# RHD2164_USBC.net
KiCad netlist of a schematic drawn in Altium Designer
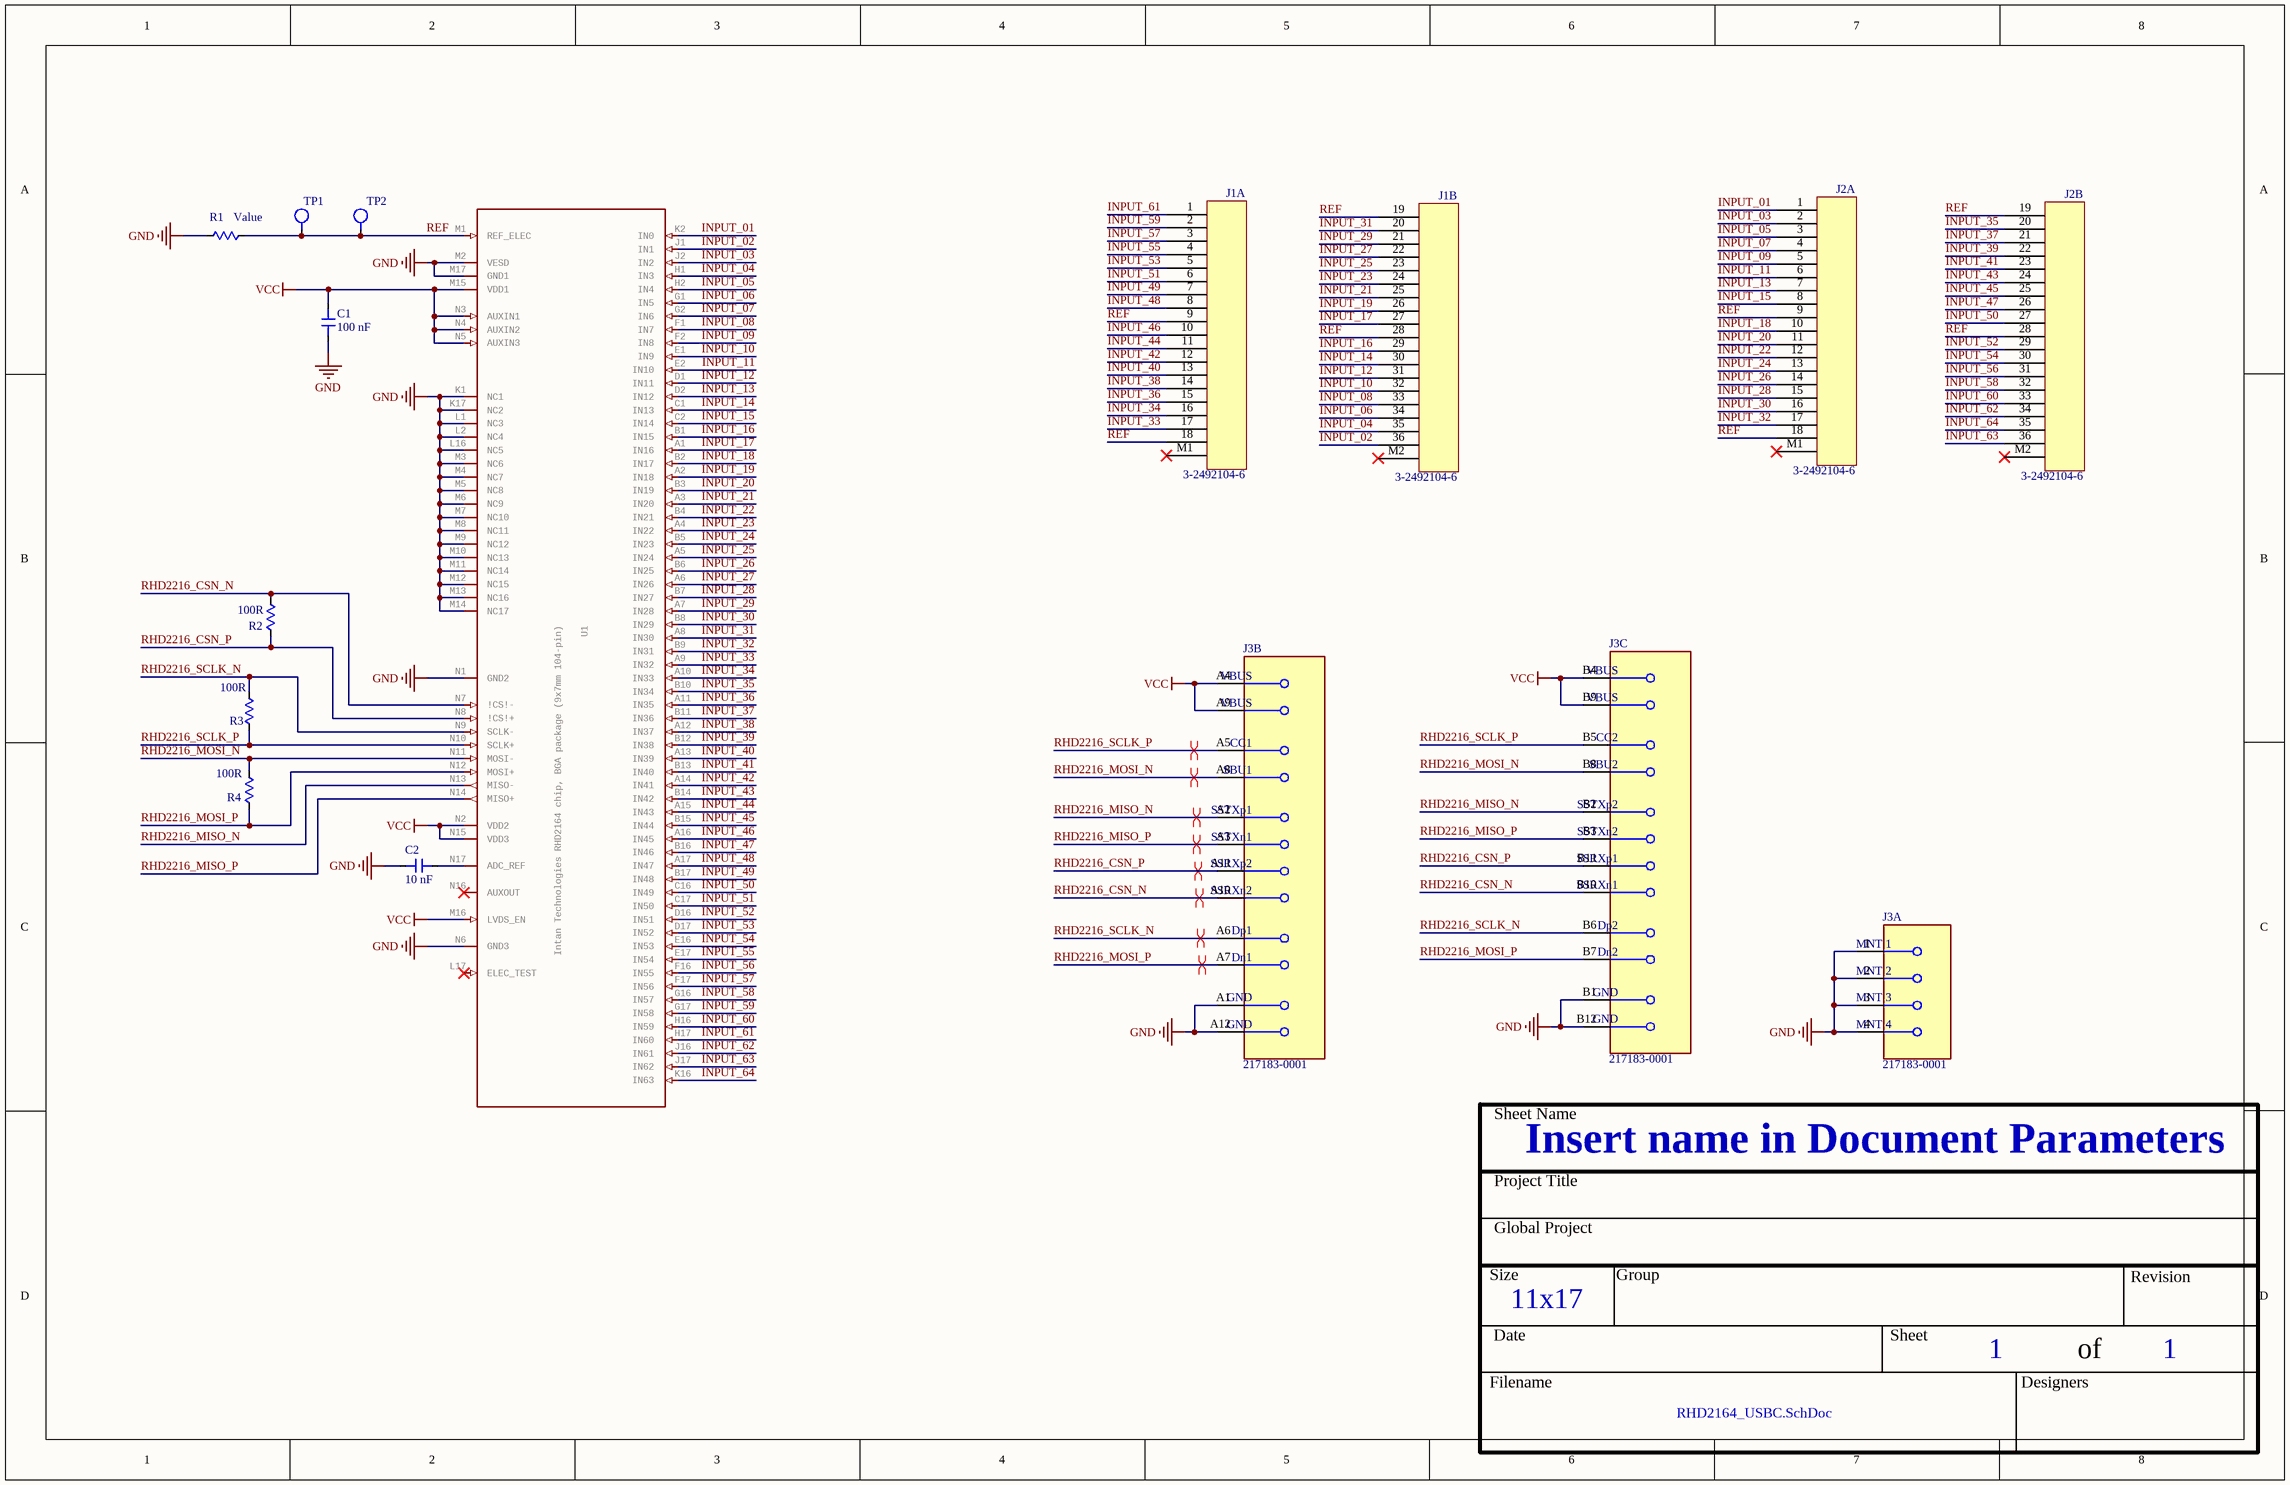
[diagram p0: RHD2164_USBC.SchDoc]

(export (version "E")
  (design (tool "Eeschema 10.0.6"))
  (components
    (comp (ref "C1")
      (value "100 nF")
      (footprint "0402_CAPACITOR")
      (description "Capacitor")
      (libsource (lib "RHD2164_USBC_V2") (part "Capacitor"))
    )
    (comp (ref "C2")
      (value "10 nF")
      (footprint "0402_CAPACITOR")
      (description "Capacitor")
      (libsource (lib "RHD2164_USBC_V2") (part "Capacitor"))
    )
    (comp (ref "J1")
      (value "3-2492104-6")
      (footprint "CON_ZIF_RA_36POS")
      (description "36 Position FPC Connector Contacts, Bottom 0.020\" (0.50mm) Surface Mount, Right Angle")
      (libsource (lib "RHD2164_USBC_V2") (part "CON_ZIF_RA_36POS"))
    )
    (comp (ref "J2")
      (value "3-2492104-6")
      (footprint "CON_ZIF_RA_36POS")
      (description "36 Position FPC Connector Contacts, Bottom 0.020\" (0.50mm) Surface Mount, Right Angle")
      (libsource (lib "RHD2164_USBC_V2") (part "CON_ZIF_RA_36POS"))
    )
    (comp (ref "J3")
      (value "217183-0001")
      (footprint "FP-217183-0001-MFG")
      (libsource (lib "Connectors") (part "CON_USBC_TH_SMT"))
    )
    (comp (ref "R1")
      (value "Value")
      (footprint "0402_Resistor")
      (description "Resistor")
      (libsource (lib "RHD2164_USBC_V2") (part "Resistor"))
    )
    (comp (ref "R2")
      (value "100R")
      (footprint "0402_Resistor")
      (description "Resistor")
      (libsource (lib "RHD2164_USBC_V2") (part "Resistor"))
    )
    (comp (ref "R3")
      (value "100R")
      (footprint "0402_Resistor")
      (description "Resistor")
      (libsource (lib "RHD2164_USBC_V2") (part "Resistor"))
    )
    (comp (ref "R4")
      (value "100R")
      (footprint "0402_Resistor")
      (description "Resistor")
      (libsource (lib "RHD2164_USBC_V2") (part "Resistor"))
    )
    (comp (ref "TP1")
      (value "TP_Small")
      (footprint "TP_Small_M2")
      (libsource (lib "RHD2164_USBC_V2") (part "TP_Small"))
    )
    (comp (ref "TP2")
      (value "TP_Small")
      (footprint "TP_Small_M2")
      (libsource (lib "RHD2164_USBC_V2") (part "TP_Small"))
    )
    (comp (ref "U1")
      (value "Intan Technologies RHD2164 chip, BGA package (9x7mm 104-pin)")
      (footprint "RHD2164_BGA")
      (libsource (lib "RHD2164_USBC_V2") (part "RHD2164_BGA_BGA"))
    )
  )
  (nets
    (net (code "1") (name "/INPUT_01") (class "Default")
      (node (ref "J2") (pin "1") (pinfunction "1_1") (pintype "passive"))
      (node (ref "U1") (pin "K2") (pinfunction "IN0_K2") (pintype "input"))
    )
    (net (code "2") (name "/INPUT_02") (class "Default")
      (node (ref "J1") (pin "36") (pinfunction "36_36") (pintype "passive"))
      (node (ref "U1") (pin "J1") (pinfunction "IN1_J1") (pintype "input"))
    )
    (net (code "3") (name "/INPUT_03") (class "Default")
      (node (ref "J2") (pin "2") (pinfunction "2_2") (pintype "passive"))
      (node (ref "U1") (pin "J2") (pinfunction "IN2_J2") (pintype "input"))
    )
    (net (code "4") (name "/INPUT_04") (class "Default")
      (node (ref "J1") (pin "35") (pinfunction "35_35") (pintype "passive"))
      (node (ref "U1") (pin "H1") (pinfunction "IN3_H1") (pintype "input"))
    )
    (net (code "5") (name "/INPUT_05") (class "Default")
      (node (ref "J2") (pin "3") (pinfunction "3_3") (pintype "passive"))
      (node (ref "U1") (pin "H2") (pinfunction "IN4_H2") (pintype "input"))
    )
    (net (code "6") (name "/INPUT_06") (class "Default")
      (node (ref "J1") (pin "34") (pinfunction "34_34") (pintype "passive"))
      (node (ref "U1") (pin "G1") (pinfunction "IN5_G1") (pintype "input"))
    )
    (net (code "7") (name "/INPUT_07") (class "Default")
      (node (ref "J2") (pin "4") (pinfunction "4_4") (pintype "passive"))
      (node (ref "U1") (pin "G2") (pinfunction "IN6_G2") (pintype "input"))
    )
    (net (code "8") (name "/INPUT_08") (class "Default")
      (node (ref "J1") (pin "33") (pinfunction "33_33") (pintype "passive"))
      (node (ref "U1") (pin "F1") (pinfunction "IN7_F1") (pintype "input"))
    )
    (net (code "9") (name "/INPUT_09") (class "Default")
      (node (ref "J2") (pin "5") (pinfunction "5_5") (pintype "passive"))
      (node (ref "U1") (pin "F2") (pinfunction "IN8_F2") (pintype "input"))
    )
    (net (code "10") (name "/INPUT_10") (class "Default")
      (node (ref "J1") (pin "32") (pinfunction "32_32") (pintype "passive"))
      (node (ref "U1") (pin "E1") (pinfunction "IN9_E1") (pintype "input"))
    )
    (net (code "11") (name "/INPUT_11") (class "Default")
      (node (ref "J2") (pin "6") (pinfunction "6_6") (pintype "passive"))
      (node (ref "U1") (pin "E2") (pinfunction "IN10_E2") (pintype "input"))
    )
    (net (code "12") (name "/INPUT_12") (class "Default")
      (node (ref "J1") (pin "31") (pinfunction "31_31") (pintype "passive"))
      (node (ref "U1") (pin "D1") (pinfunction "IN11_D1") (pintype "input"))
    )
    (net (code "13") (name "/INPUT_13") (class "Default")
      (node (ref "J2") (pin "7") (pinfunction "7_7") (pintype "passive"))
      (node (ref "U1") (pin "D2") (pinfunction "IN12_D2") (pintype "input"))
    )
    (net (code "14") (name "/INPUT_14") (class "Default")
      (node (ref "J1") (pin "30") (pinfunction "30_30") (pintype "passive"))
      (node (ref "U1") (pin "C1") (pinfunction "IN13_C1") (pintype "input"))
    )
    (net (code "15") (name "/INPUT_15") (class "Default")
      (node (ref "J2") (pin "8") (pinfunction "8_8") (pintype "passive"))
      (node (ref "U1") (pin "C2") (pinfunction "IN14_C2") (pintype "input"))
    )
    (net (code "16") (name "/INPUT_16") (class "Default")
      (node (ref "J1") (pin "29") (pinfunction "29_29") (pintype "passive"))
      (node (ref "U1") (pin "B1") (pinfunction "IN15_B1") (pintype "input"))
    )
    (net (code "17") (name "/INPUT_17") (class "Default")
      (node (ref "J1") (pin "27") (pinfunction "27_27") (pintype "passive"))
      (node (ref "U1") (pin "A1") (pinfunction "IN16_A1") (pintype "input"))
    )
    (net (code "18") (name "/INPUT_18") (class "Default")
      (node (ref "J2") (pin "10") (pinfunction "10_10") (pintype "passive"))
      (node (ref "U1") (pin "B2") (pinfunction "IN17_B2") (pintype "input"))
    )
    (net (code "19") (name "/INPUT_19") (class "Default")
      (node (ref "J1") (pin "26") (pinfunction "26_26") (pintype "passive"))
      (node (ref "U1") (pin "A2") (pinfunction "IN18_A2") (pintype "input"))
    )
    (net (code "20") (name "/INPUT_20") (class "Default")
      (node (ref "J2") (pin "11") (pinfunction "11_11") (pintype "passive"))
      (node (ref "U1") (pin "B3") (pinfunction "IN19_B3") (pintype "input"))
    )
    (net (code "21") (name "/INPUT_21") (class "Default")
      (node (ref "J1") (pin "25") (pinfunction "25_25") (pintype "passive"))
      (node (ref "U1") (pin "A3") (pinfunction "IN20_A3") (pintype "input"))
    )
    (net (code "22") (name "/INPUT_22") (class "Default")
      (node (ref "J2") (pin "12") (pinfunction "12_12") (pintype "passive"))
      (node (ref "U1") (pin "B4") (pinfunction "IN21_B4") (pintype "input"))
    )
    (net (code "23") (name "/INPUT_23") (class "Default")
      (node (ref "J1") (pin "24") (pinfunction "24_24") (pintype "passive"))
      (node (ref "U1") (pin "A4") (pinfunction "IN22_A4") (pintype "input"))
    )
    (net (code "24") (name "/INPUT_24") (class "Default")
      (node (ref "J2") (pin "13") (pinfunction "13_13") (pintype "passive"))
      (node (ref "U1") (pin "B5") (pinfunction "IN23_B5") (pintype "input"))
    )
    (net (code "25") (name "/INPUT_25") (class "Default")
      (node (ref "J1") (pin "23") (pinfunction "23_23") (pintype "passive"))
      (node (ref "U1") (pin "A5") (pinfunction "IN24_A5") (pintype "input"))
    )
    (net (code "26") (name "/INPUT_26") (class "Default")
      (node (ref "J2") (pin "14") (pinfunction "14_14") (pintype "passive"))
      (node (ref "U1") (pin "B6") (pinfunction "IN25_B6") (pintype "input"))
    )
    (net (code "27") (name "/INPUT_27") (class "Default")
      (node (ref "J1") (pin "22") (pinfunction "22_22") (pintype "passive"))
      (node (ref "U1") (pin "A6") (pinfunction "IN26_A6") (pintype "input"))
    )
    (net (code "28") (name "/INPUT_28") (class "Default")
      (node (ref "J2") (pin "15") (pinfunction "15_15") (pintype "passive"))
      (node (ref "U1") (pin "B7") (pinfunction "IN27_B7") (pintype "input"))
    )
    (net (code "29") (name "/INPUT_29") (class "Default")
      (node (ref "J1") (pin "21") (pinfunction "21_21") (pintype "passive"))
      (node (ref "U1") (pin "A7") (pinfunction "IN28_A7") (pintype "input"))
    )
    (net (code "30") (name "/INPUT_30") (class "Default")
      (node (ref "J2") (pin "16") (pinfunction "16_16") (pintype "passive"))
      (node (ref "U1") (pin "B8") (pinfunction "IN29_B8") (pintype "input"))
    )
    (net (code "31") (name "/INPUT_31") (class "Default")
      (node (ref "J1") (pin "20") (pinfunction "20_20") (pintype "passive"))
      (node (ref "U1") (pin "A8") (pinfunction "IN30_A8") (pintype "input"))
    )
    (net (code "32") (name "/INPUT_32") (class "Default")
      (node (ref "J2") (pin "17") (pinfunction "17_17") (pintype "passive"))
      (node (ref "U1") (pin "B9") (pinfunction "IN31_B9") (pintype "input"))
    )
    (net (code "33") (name "/INPUT_33") (class "Default")
      (node (ref "J1") (pin "17") (pinfunction "17_17") (pintype "passive"))
      (node (ref "U1") (pin "A9") (pinfunction "IN32_A9") (pintype "input"))
    )
    (net (code "34") (name "/INPUT_34") (class "Default")
      (node (ref "J1") (pin "16") (pinfunction "16_16") (pintype "passive"))
      (node (ref "U1") (pin "A10") (pinfunction "IN33_A10") (pintype "input"))
    )
    (net (code "35") (name "/INPUT_35") (class "Default")
      (node (ref "J2") (pin "20") (pinfunction "20_20") (pintype "passive"))
      (node (ref "U1") (pin "B10") (pinfunction "IN34_B10") (pintype "input"))
    )
    (net (code "36") (name "/INPUT_36") (class "Default")
      (node (ref "J1") (pin "15") (pinfunction "15_15") (pintype "passive"))
      (node (ref "U1") (pin "A11") (pinfunction "IN35_A11") (pintype "input"))
    )
    (net (code "37") (name "/INPUT_37") (class "Default")
      (node (ref "J2") (pin "21") (pinfunction "21_21") (pintype "passive"))
      (node (ref "U1") (pin "B11") (pinfunction "IN36_B11") (pintype "input"))
    )
    (net (code "38") (name "/INPUT_38") (class "Default")
      (node (ref "J1") (pin "14") (pinfunction "14_14") (pintype "passive"))
      (node (ref "U1") (pin "A12") (pinfunction "IN37_A12") (pintype "input"))
    )
    (net (code "39") (name "/INPUT_39") (class "Default")
      (node (ref "J2") (pin "22") (pinfunction "22_22") (pintype "passive"))
      (node (ref "U1") (pin "B12") (pinfunction "IN38_B12") (pintype "input"))
    )
    (net (code "40") (name "/INPUT_40") (class "Default")
      (node (ref "J1") (pin "13") (pinfunction "13_13") (pintype "passive"))
      (node (ref "U1") (pin "A13") (pinfunction "IN39_A13") (pintype "input"))
    )
    (net (code "41") (name "/INPUT_41") (class "Default")
      (node (ref "J2") (pin "23") (pinfunction "23_23") (pintype "passive"))
      (node (ref "U1") (pin "B13") (pinfunction "IN40_B13") (pintype "input"))
    )
    (net (code "42") (name "/INPUT_42") (class "Default")
      (node (ref "J1") (pin "12") (pinfunction "12_12") (pintype "passive"))
      (node (ref "U1") (pin "A14") (pinfunction "IN41_A14") (pintype "input"))
    )
    (net (code "43") (name "/INPUT_43") (class "Default")
      (node (ref "J2") (pin "24") (pinfunction "24_24") (pintype "passive"))
      (node (ref "U1") (pin "B14") (pinfunction "IN42_B14") (pintype "input"))
    )
    (net (code "44") (name "/INPUT_44") (class "Default")
      (node (ref "J1") (pin "11") (pinfunction "11_11") (pintype "passive"))
      (node (ref "U1") (pin "A15") (pinfunction "IN43_A15") (pintype "input"))
    )
    (net (code "45") (name "/INPUT_45") (class "Default")
      (node (ref "J2") (pin "25") (pinfunction "25_25") (pintype "passive"))
      (node (ref "U1") (pin "B15") (pinfunction "IN44_B15") (pintype "input"))
    )
    (net (code "46") (name "/INPUT_46") (class "Default")
      (node (ref "J1") (pin "10") (pinfunction "10_10") (pintype "passive"))
      (node (ref "U1") (pin "A16") (pinfunction "IN45_A16") (pintype "input"))
    )
    (net (code "47") (name "/INPUT_47") (class "Default")
      (node (ref "J2") (pin "26") (pinfunction "26_26") (pintype "passive"))
      (node (ref "U1") (pin "B16") (pinfunction "IN46_B16") (pintype "input"))
    )
    (net (code "48") (name "/INPUT_48") (class "Default")
      (node (ref "J1") (pin "8") (pinfunction "8_8") (pintype "passive"))
      (node (ref "U1") (pin "A17") (pinfunction "IN47_A17") (pintype "input"))
    )
    (net (code "49") (name "/INPUT_49") (class "Default")
      (node (ref "J1") (pin "7") (pinfunction "7_7") (pintype "passive"))
      (node (ref "U1") (pin "B17") (pinfunction "IN48_B17") (pintype "input"))
    )
    (net (code "50") (name "/INPUT_50") (class "Default")
      (node (ref "J2") (pin "27") (pinfunction "27_27") (pintype "passive"))
      (node (ref "U1") (pin "C16") (pinfunction "IN49_C16") (pintype "input"))
    )
    (net (code "51") (name "/INPUT_51") (class "Default")
      (node (ref "J1") (pin "6") (pinfunction "6_6") (pintype "passive"))
      (node (ref "U1") (pin "C17") (pinfunction "IN50_C17") (pintype "input"))
    )
    (net (code "52") (name "/INPUT_52") (class "Default")
      (node (ref "J2") (pin "29") (pinfunction "29_29") (pintype "passive"))
      (node (ref "U1") (pin "D16") (pinfunction "IN51_D16") (pintype "input"))
    )
    (net (code "53") (name "/INPUT_53") (class "Default")
      (node (ref "J1") (pin "5") (pinfunction "5_5") (pintype "passive"))
      (node (ref "U1") (pin "D17") (pinfunction "IN52_D17") (pintype "input"))
    )
    (net (code "54") (name "/INPUT_54") (class "Default")
      (node (ref "J2") (pin "30") (pinfunction "30_30") (pintype "passive"))
      (node (ref "U1") (pin "E16") (pinfunction "IN53_E16") (pintype "input"))
    )
    (net (code "55") (name "/INPUT_55") (class "Default")
      (node (ref "J1") (pin "4") (pinfunction "4_4") (pintype "passive"))
      (node (ref "U1") (pin "E17") (pinfunction "IN54_E17") (pintype "input"))
    )
    (net (code "56") (name "/INPUT_56") (class "Default")
      (node (ref "J2") (pin "31") (pinfunction "31_31") (pintype "passive"))
      (node (ref "U1") (pin "F16") (pinfunction "IN55_F16") (pintype "input"))
    )
    (net (code "57") (name "/INPUT_57") (class "Default")
      (node (ref "J1") (pin "3") (pinfunction "3_3") (pintype "passive"))
      (node (ref "U1") (pin "F17") (pinfunction "IN56_F17") (pintype "input"))
    )
    (net (code "58") (name "/INPUT_58") (class "Default")
      (node (ref "J2") (pin "32") (pinfunction "32_32") (pintype "passive"))
      (node (ref "U1") (pin "G16") (pinfunction "IN57_G16") (pintype "input"))
    )
    (net (code "59") (name "/INPUT_59") (class "Default")
      (node (ref "J1") (pin "2") (pinfunction "2_2") (pintype "passive"))
      (node (ref "U1") (pin "G17") (pinfunction "IN58_G17") (pintype "input"))
    )
    (net (code "60") (name "/INPUT_60") (class "Default")
      (node (ref "J2") (pin "33") (pinfunction "33_33") (pintype "passive"))
      (node (ref "U1") (pin "H16") (pinfunction "IN59_H16") (pintype "input"))
    )
    (net (code "61") (name "/INPUT_61") (class "Default")
      (node (ref "J1") (pin "1") (pinfunction "1_1") (pintype "passive"))
      (node (ref "U1") (pin "H17") (pinfunction "IN60_H17") (pintype "input"))
    )
    (net (code "62") (name "/INPUT_62") (class "Default")
      (node (ref "J2") (pin "34") (pinfunction "34_34") (pintype "passive"))
      (node (ref "U1") (pin "J16") (pinfunction "IN61_J16") (pintype "input"))
    )
    (net (code "63") (name "/INPUT_63") (class "Default")
      (node (ref "J2") (pin "36") (pinfunction "36_36") (pintype "passive"))
      (node (ref "U1") (pin "J17") (pinfunction "IN62_J17") (pintype "input"))
    )
    (net (code "64") (name "/INPUT_64") (class "Default")
      (node (ref "J2") (pin "35") (pinfunction "35_35") (pintype "passive"))
      (node (ref "U1") (pin "K16") (pinfunction "IN63_K16") (pintype "input"))
    )
    (net (code "65") (name "/REF") (class "Default")
      (node (ref "J1") (pin "18") (pinfunction "18_18") (pintype "passive"))
      (node (ref "J1") (pin "19") (pinfunction "19_19") (pintype "passive"))
      (node (ref "J1") (pin "28") (pinfunction "28_28") (pintype "passive"))
      (node (ref "J1") (pin "9") (pinfunction "9_9") (pintype "passive"))
      (node (ref "J2") (pin "18") (pinfunction "18_18") (pintype "passive"))
      (node (ref "J2") (pin "19") (pinfunction "19_19") (pintype "passive"))
      (node (ref "J2") (pin "28") (pinfunction "28_28") (pintype "passive"))
      (node (ref "J2") (pin "9") (pinfunction "9_9") (pintype "passive"))
      (node (ref "R1") (pin "2") (pinfunction "2_2") (pintype "passive"))
      (node (ref "TP1") (pin "1") (pinfunction "1_1") (pintype "passive"))
      (node (ref "TP2") (pin "1") (pinfunction "1_1") (pintype "passive"))
      (node (ref "U1") (pin "M1") (pinfunction "REF_ELEC_M1") (pintype "input"))
    )
    (net (code "66") (name "/RHD2216_CSN_N") (class "Default")
      (node (ref "J3") (pin "A10") (pinfunction "SSRXn2_A10") (pintype "passive"))
      (node (ref "J3") (pin "B10") (pinfunction "SSRXn1_B10") (pintype "passive"))
      (node (ref "R2") (pin "2") (pinfunction "2_2") (pintype "passive"))
      (node (ref "U1") (pin "N7") (pinfunction "!CS!-_N7") (pintype "input"))
    )
    (net (code "67") (name "/RHD2216_CSN_P") (class "Default")
      (node (ref "J3") (pin "A11") (pinfunction "SSRXp2_A11") (pintype "passive"))
      (node (ref "J3") (pin "B11") (pinfunction "SSRXp1_B11") (pintype "passive"))
      (node (ref "R2") (pin "1") (pinfunction "1_1") (pintype "passive"))
      (node (ref "U1") (pin "N8") (pinfunction "!CS!+_N8") (pintype "input"))
    )
    (net (code "68") (name "/RHD2216_MISO_N") (class "Default")
      (node (ref "J3") (pin "A2") (pinfunction "SSTXp1_A2") (pintype "passive"))
      (node (ref "J3") (pin "B2") (pinfunction "SSTXp2_B2") (pintype "passive"))
      (node (ref "U1") (pin "N13") (pinfunction "MISO-_N13") (pintype "output"))
    )
    (net (code "69") (name "/RHD2216_MISO_P") (class "Default")
      (node (ref "J3") (pin "A3") (pinfunction "SSTXn1_A3") (pintype "passive"))
      (node (ref "J3") (pin "B3") (pinfunction "SSTXn2_B3") (pintype "passive"))
      (node (ref "U1") (pin "N14") (pinfunction "MISO+_N14") (pintype "output"))
    )
    (net (code "70") (name "/RHD2216_MOSI_N") (class "Default")
      (node (ref "J3") (pin "A8") (pinfunction "SBU1_A8") (pintype "passive"))
      (node (ref "J3") (pin "B8") (pinfunction "SBU2_B8") (pintype "passive"))
      (node (ref "R4") (pin "2") (pinfunction "2_2") (pintype "passive"))
      (node (ref "U1") (pin "N11") (pinfunction "MOSI-_N11") (pintype "input"))
    )
    (net (code "71") (name "/RHD2216_MOSI_P") (class "Default")
      (node (ref "J3") (pin "A7") (pinfunction "Dn1_A7") (pintype "passive"))
      (node (ref "J3") (pin "B7") (pinfunction "Dn2_B7") (pintype "passive"))
      (node (ref "R4") (pin "1") (pinfunction "1_1") (pintype "passive"))
      (node (ref "U1") (pin "N12") (pinfunction "MOSI+_N12") (pintype "input"))
    )
    (net (code "72") (name "/RHD2216_SCLK_N") (class "Default")
      (node (ref "J3") (pin "A6") (pinfunction "Dp1_A6") (pintype "passive"))
      (node (ref "J3") (pin "B6") (pinfunction "Dp2_B6") (pintype "passive"))
      (node (ref "R3") (pin "2") (pinfunction "2_2") (pintype "passive"))
      (node (ref "U1") (pin "N9") (pinfunction "SCLK-_N9") (pintype "input"))
    )
    (net (code "73") (name "/RHD2216_SCLK_P") (class "Default")
      (node (ref "J3") (pin "A5") (pinfunction "CC1_A5") (pintype "passive"))
      (node (ref "J3") (pin "B5") (pinfunction "CC2_B5") (pintype "passive"))
      (node (ref "R3") (pin "1") (pinfunction "1_1") (pintype "passive"))
      (node (ref "U1") (pin "N10") (pinfunction "SCLK+_N10") (pintype "input"))
    )
    (net (code "74") (name "GND") (class "Default")
      (node (ref "C1") (pin "1") (pinfunction "1_1") (pintype "passive"))
      (node (ref "C2") (pin "2") (pinfunction "2_2") (pintype "passive"))
      (node (ref "J3") (pin "1") (pinfunction "MNT_1_1") (pintype "passive"))
      (node (ref "J3") (pin "2") (pinfunction "MNT_2_2") (pintype "passive"))
      (node (ref "J3") (pin "3") (pinfunction "MNT_3_3") (pintype "passive"))
      (node (ref "J3") (pin "4") (pinfunction "MNT_4_4") (pintype "passive"))
      (node (ref "J3") (pin "A1") (pinfunction "GND_A1") (pintype "passive"))
      (node (ref "J3") (pin "A12") (pinfunction "GND_A12") (pintype "passive"))
      (node (ref "J3") (pin "B1") (pinfunction "GND_B1") (pintype "passive"))
      (node (ref "J3") (pin "B12") (pinfunction "GND_B12") (pintype "passive"))
      (node (ref "R1") (pin "1") (pinfunction "1_1") (pintype "passive"))
      (node (ref "U1") (pin "K1") (pinfunction "NC1_K1") (pintype "passive"))
      (node (ref "U1") (pin "K17") (pinfunction "NC2_K17") (pintype "passive"))
      (node (ref "U1") (pin "L1") (pinfunction "NC3_L1") (pintype "passive"))
      (node (ref "U1") (pin "L16") (pinfunction "NC5_L16") (pintype "passive"))
      (node (ref "U1") (pin "L2") (pinfunction "NC4_L2") (pintype "passive"))
      (node (ref "U1") (pin "M10") (pinfunction "NC13_M10") (pintype "passive"))
      (node (ref "U1") (pin "M11") (pinfunction "NC14_M11") (pintype "passive"))
      (node (ref "U1") (pin "M12") (pinfunction "NC15_M12") (pintype "passive"))
      (node (ref "U1") (pin "M13") (pinfunction "NC16_M13") (pintype "passive"))
      (node (ref "U1") (pin "M14") (pinfunction "NC17_M14") (pintype "passive"))
      (node (ref "U1") (pin "M17") (pinfunction "GND1_M17") (pintype "power_in"))
      (node (ref "U1") (pin "M2") (pinfunction "VESD_M2") (pintype "power_in"))
      (node (ref "U1") (pin "M3") (pinfunction "NC6_M3") (pintype "passive"))
      (node (ref "U1") (pin "M4") (pinfunction "NC7_M4") (pintype "passive"))
      (node (ref "U1") (pin "M5") (pinfunction "NC8_M5") (pintype "passive"))
      (node (ref "U1") (pin "M6") (pinfunction "NC9_M6") (pintype "passive"))
      (node (ref "U1") (pin "M7") (pinfunction "NC10_M7") (pintype "passive"))
      (node (ref "U1") (pin "M8") (pinfunction "NC11_M8") (pintype "passive"))
      (node (ref "U1") (pin "M9") (pinfunction "NC12_M9") (pintype "passive"))
      (node (ref "U1") (pin "N1") (pinfunction "GND2_N1") (pintype "power_in"))
      (node (ref "U1") (pin "N6") (pinfunction "GND3_N6") (pintype "power_in"))
    )
    (net (code "75") (name "Net-(U1-ADC_REF)") (class "Default")
      (node (ref "C2") (pin "1") (pinfunction "1_1") (pintype "passive"))
      (node (ref "U1") (pin "N17") (pinfunction "ADC_REF_N17") (pintype "passive"))
    )
    (net (code "76") (name "VCC") (class "Default")
      (node (ref "C1") (pin "2") (pinfunction "2_2") (pintype "passive"))
      (node (ref "J3") (pin "A4") (pinfunction "VBUS_A4") (pintype "passive"))
      (node (ref "J3") (pin "A9") (pinfunction "VBUS_A9") (pintype "passive"))
      (node (ref "J3") (pin "B4") (pinfunction "VBUS_B4") (pintype "passive"))
      (node (ref "J3") (pin "B9") (pinfunction "VBUS_B9") (pintype "passive"))
      (node (ref "U1") (pin "M15") (pinfunction "VDD1_M15") (pintype "power_in"))
      (node (ref "U1") (pin "M16") (pinfunction "LVDS_EN_M16") (pintype "input"))
      (node (ref "U1") (pin "N15") (pinfunction "VDD3_N15") (pintype "power_in"))
      (node (ref "U1") (pin "N2") (pinfunction "VDD2_N2") (pintype "power_in"))
      (node (ref "U1") (pin "N3") (pinfunction "AUXIN1_N3") (pintype "input"))
      (node (ref "U1") (pin "N4") (pinfunction "AUXIN2_N4") (pintype "input"))
      (node (ref "U1") (pin "N5") (pinfunction "AUXIN3_N5") (pintype "input"))
    )
    (net (code "77") (name "unconnected-(J1-PadM1)") (class "Default")
      (node (ref "J1") (pin "M1") (pinfunction "M1_M1") (pintype "passive+no_connect"))
    )
    (net (code "78") (name "unconnected-(J1-PadM2)") (class "Default")
      (node (ref "J1") (pin "M2") (pinfunction "M2_M2") (pintype "passive+no_connect"))
    )
    (net (code "79") (name "unconnected-(J2-PadM1)") (class "Default")
      (node (ref "J2") (pin "M1") (pinfunction "M1_M1") (pintype "passive+no_connect"))
    )
    (net (code "80") (name "unconnected-(J2-PadM2)") (class "Default")
      (node (ref "J2") (pin "M2") (pinfunction "M2_M2") (pintype "passive+no_connect"))
    )
    (net (code "81") (name "unconnected-(U1-AUXOUT-PadN16)") (class "Default")
      (node (ref "U1") (pin "N16") (pinfunction "AUXOUT_N16") (pintype "tri_state+no_connect"))
    )
    (net (code "82") (name "unconnected-(U1-ELEC_TEST-PadL17)") (class "Default")
      (node (ref "U1") (pin "L17") (pinfunction "ELEC_TEST_L17") (pintype "input+no_connect"))
    )
  )
)
